# Gondola_Sail_electronics_M4_minimal.net
KiCad netlist of a schematic drawn in EAGLE
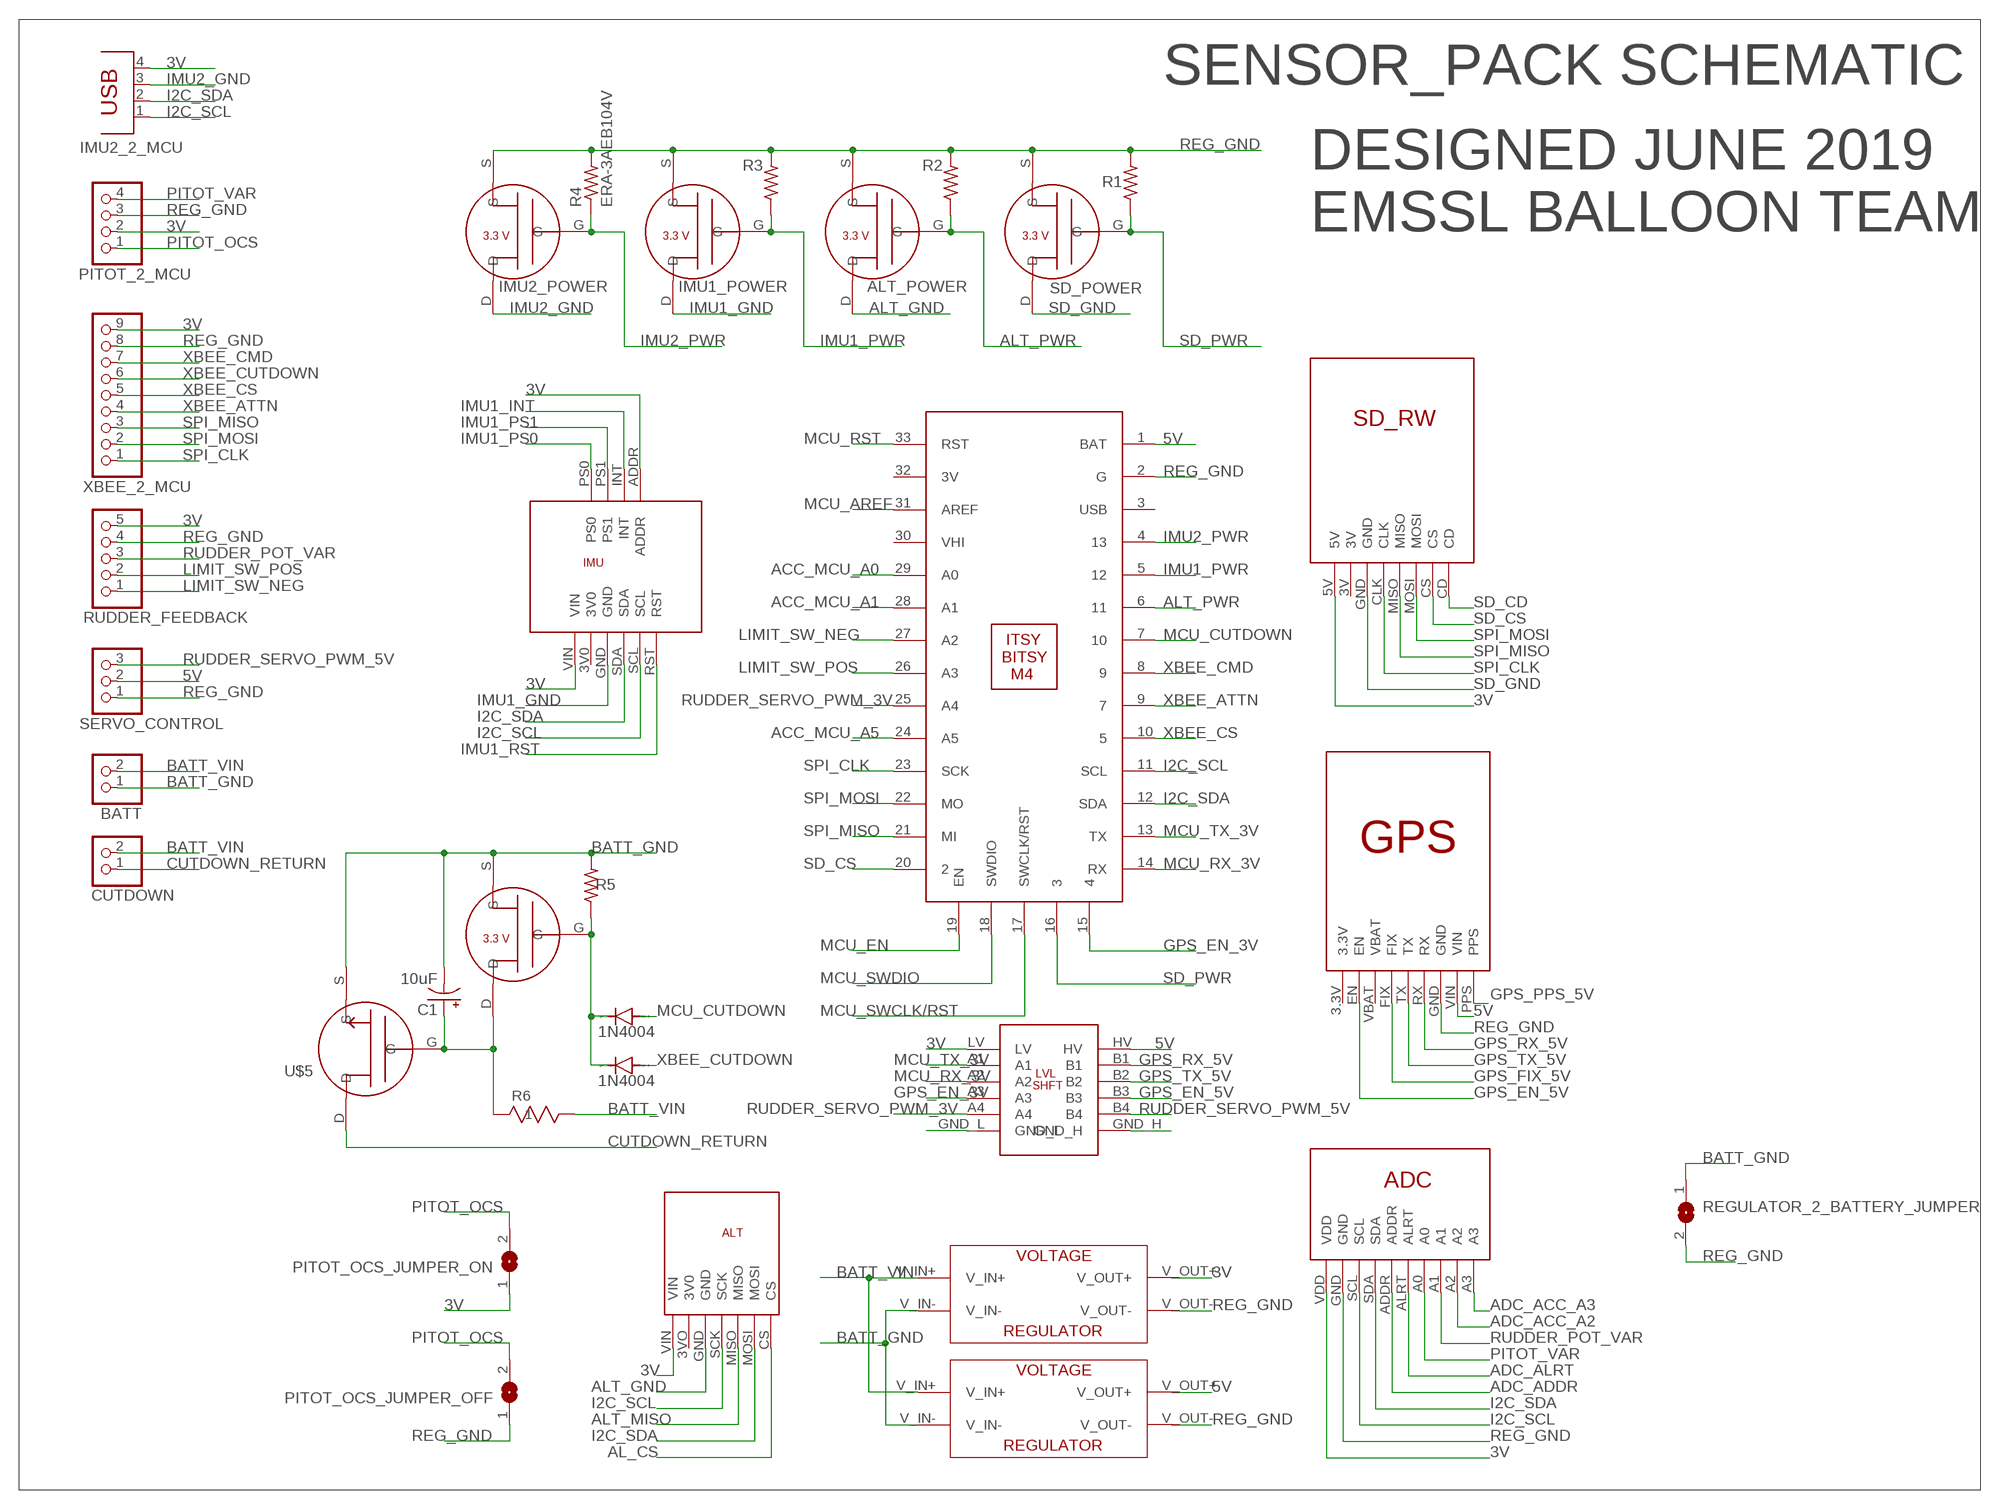
[diagram p0: schematic, sheet 1]

(export (version "E")
  (design (tool "Eeschema 10.0.6"))
  (components
    (comp (ref "3V_REG")
      (value "3V/5V_REGULATOR")
      (footprint "eagle-import:5V_3V_REGULATOR")
      (libsource (lib "eagle-import") (part "3V/5V_REGULATOR"))
    )
    (comp (ref "5V_REG")
      (value "3V/5V_REGULATOR")
      (footprint "eagle-import:5V_3V_REGULATOR")
      (libsource (lib "eagle-import") (part "3V/5V_REGULATOR"))
    )
    (comp (ref "ALT_POWER")
      (value "3.3V_NCH_FET")
      (footprint "eagle-import:3.3VTRANSISTOR")
      (libsource (lib "eagle-import") (part "3.3V_NCH_FET"))
    )
    (comp (ref "BATT")
      (value "PINHD-1X2/90")
      (footprint "eagle-import:1X02_90")
      (libsource (lib "eagle-import") (part "PINHD-1X2/90"))
    )
    (comp (ref "C1")
      (value "10uF")
      (footprint "eagle-import:CPOL-RADIAL-2.5MM-5MM")
      (libsource (lib "eagle-import") (part "10UF-POLAR-RADIAL-2.5MM-25V-20%"))
    )
    (comp (ref "CUTDOWN")
      (value "PINHD-1X2/90")
      (footprint "eagle-import:1X02_90")
      (libsource (lib "eagle-import") (part "PINHD-1X2/90"))
    )
    (comp (ref "D1")
      (value "1N4004")
      (footprint "eagle-import:DO41-10")
      (libsource (lib "eagle-import") (part "1N4004"))
    )
    (comp (ref "D2")
      (value "1N4004")
      (footprint "eagle-import:DO41-10")
      (libsource (lib "eagle-import") (part "1N4004"))
    )
    (comp (ref "IMU1")
      (value "BNO055")
      (footprint "eagle-import:BNO055")
      (libsource (lib "eagle-import") (part "BNO055"))
    )
    (comp (ref "IMU1_POWER")
      (value "3.3V_NCH_FET")
      (footprint "eagle-import:3.3VTRANSISTOR")
      (libsource (lib "eagle-import") (part "3.3V_NCH_FET"))
    )
    (comp (ref "IMU2_2_MCU")
      (value "PN87520")
      (footprint "eagle-import:PN87520")
      (libsource (lib "eagle-import") (part "PN87520"))
    )
    (comp (ref "IMU2_POWER")
      (value "3.3V_NCH_FET")
      (footprint "eagle-import:3.3VTRANSISTOR")
      (libsource (lib "eagle-import") (part "3.3V_NCH_FET"))
    )
    (comp (ref "PITOT_2_MCU")
      (value "PINHD-1X4/90")
      (footprint "eagle-import:1X04_90")
      (libsource (lib "eagle-import") (part "PINHD-1X4/90"))
    )
    (comp (ref "PITOT_OCS_JUMPER_OFF")
      (value "SJ")
      (footprint "eagle-import:SJ")
      (libsource (lib "eagle-import") (part "SJ"))
    )
    (comp (ref "PITOT_OCS_JUMPER_ON")
      (value "SJ")
      (footprint "eagle-import:SJ")
      (libsource (lib "eagle-import") (part "SJ"))
    )
    (comp (ref "R1")
      (value "ERA-3AEB104V")
      (footprint "eagle-import:RESC1608X55")
      (fields (field (name "DIGI-KEY_PART_NUMBER") "P100KDBCT-ND") (field (name "MF") "Panasonic"))
      (libsource (lib "eagle-import") (part "ERA-3AEB104V"))
    )
    (comp (ref "R2")
      (value "ERA-3AEB104V")
      (footprint "eagle-import:RESC1608X55")
      (fields (field (name "DIGI-KEY_PART_NUMBER") "P100KDBCT-ND") (field (name "MF") "Panasonic"))
      (libsource (lib "eagle-import") (part "ERA-3AEB104V"))
    )
    (comp (ref "R3")
      (value "ERA-3AEB104V")
      (footprint "eagle-import:RESC1608X55")
      (fields (field (name "DIGI-KEY_PART_NUMBER") "P100KDBCT-ND") (field (name "MF") "Panasonic"))
      (libsource (lib "eagle-import") (part "ERA-3AEB104V"))
    )
    (comp (ref "R4")
      (value "ERA-3AEB104V")
      (footprint "eagle-import:RESC1608X55")
      (fields (field (name "DIGI-KEY_PART_NUMBER") "P100KDBCT-ND") (field (name "MF") "Panasonic"))
      (libsource (lib "eagle-import") (part "ERA-3AEB104V"))
    )
    (comp (ref "R5")
      (value "ERA-3AEB104V")
      (footprint "eagle-import:RESC1608X55")
      (fields (field (name "DIGI-KEY_PART_NUMBER") "P100KDBCT-ND") (field (name "MF") "Panasonic"))
      (libsource (lib "eagle-import") (part "ERA-3AEB104V"))
    )
    (comp (ref "R6")
      (value "RR0816P-103-D")
      (footprint "eagle-import:RES_0816")
      (fields (field (name "MANUFACTURER_PART_NUMBER") "RR0816P103D"))
      (libsource (lib "eagle-import") (part "RR0816P-103-D"))
    )
    (comp (ref "REGULATOR_2_BATTERY_JUMPER")
      (value "SJW")
      (footprint "eagle-import:SJW")
      (libsource (lib "eagle-import") (part "SJW"))
    )
    (comp (ref "RUDDER_FEEDBACK")
      (value "PINHD-1X5/90")
      (footprint "eagle-import:1X05_90")
      (libsource (lib "eagle-import") (part "PINHD-1X5/90"))
    )
    (comp (ref "SD_POWER")
      (value "3.3V_NCH_FET")
      (footprint "eagle-import:3.3VTRANSISTOR")
      (libsource (lib "eagle-import") (part "3.3V_NCH_FET"))
    )
    (comp (ref "SD_POWER1")
      (value "3.3V_NCH_FET")
      (footprint "eagle-import:3.3VTRANSISTOR")
      (libsource (lib "eagle-import") (part "3.3V_NCH_FET"))
    )
    (comp (ref "SERVO_CONTROL")
      (value "PINHD-1X3/90")
      (footprint "eagle-import:1X03_90")
      (libsource (lib "eagle-import") (part "PINHD-1X3/90"))
    )
    (comp (ref "U$1")
      (value "ADAFRUIT_GPS")
      (footprint "eagle-import:ADAFRUIT_GPS")
      (libsource (lib "eagle-import") (part "ADAFRUIT_GPS"))
    )
    (comp (ref "U$2")
      (value "ADAFRUI_SD_RW")
      (footprint "eagle-import:ADAFRUIT_SD_RW")
      (libsource (lib "eagle-import") (part "ADAFRUI_SD_RW"))
    )
    (comp (ref "U$3")
      (value "ADS1115")
      (footprint "eagle-import:ADS1115")
      (libsource (lib "eagle-import") (part "ADS1115"))
    )
    (comp (ref "U$4")
      (value "BME280")
      (footprint "eagle-import:BME280")
      (libsource (lib "eagle-import") (part "BME280"))
    )
    (comp (ref "U$5")
      (value "CUTDOWN_POWER_TRANSISTOR")
      (footprint "eagle-import:T03B")
      (libsource (lib "eagle-import") (part "CUTDOWN_POWER_TRANSISTOR"))
    )
    (comp (ref "U$6")
      (value "BSS138_LVLSHIFT")
      (footprint "eagle-import:BSS138_LEVELSHIFT")
      (libsource (lib "eagle-import") (part "BSS138_LVLSHIFT"))
    )
    (comp (ref "U$8")
      (value "ITSY_BITSY_M4")
      (footprint "eagle-import:ITSY_BITSY_M4")
      (libsource (lib "eagle-import") (part "ITSY_BITSY_M4"))
    )
    (comp (ref "XBEE_2_MCU")
      (value "PINHD-1X9/90")
      (footprint "eagle-import:1X09_90")
      (libsource (lib "eagle-import") (part "PINHD-1X9/90"))
    )
  )
  (nets
    (net (code "1") (name "/3V") (class "Default")
      (node (ref "3V_REG") (pin "V_OUT+") (pinfunction "V_OUT+_V_OUT+") (pintype "bidirectional"))
      (node (ref "IMU1") (pin "ADDR") (pinfunction "ADDR_ADDR") (pintype "bidirectional"))
      (node (ref "IMU1") (pin "VIN") (pinfunction "VIN_VIN") (pintype "bidirectional"))
      (node (ref "IMU2_2_MCU") (pin "4") (pinfunction "4_4") (pintype "passive"))
      (node (ref "PITOT_2_MCU") (pin "2") (pinfunction "2_2") (pintype "passive"))
      (node (ref "PITOT_OCS_JUMPER_ON") (pin "1") (pinfunction "1_1") (pintype "passive"))
      (node (ref "RUDDER_FEEDBACK") (pin "5") (pinfunction "5_5") (pintype "passive"))
      (node (ref "U$2") (pin "5V") (pinfunction "5V_5V") (pintype "bidirectional"))
      (node (ref "U$3") (pin "VDD") (pinfunction "VDD_VDD") (pintype "bidirectional"))
      (node (ref "U$4") (pin "VIN") (pinfunction "VIN_VIN") (pintype "bidirectional"))
      (node (ref "U$6") (pin "LV") (pinfunction "LV_LV") (pintype "bidirectional"))
      (node (ref "XBEE_2_MCU") (pin "9") (pinfunction "9_9") (pintype "passive"))
    )
    (net (code "2") (name "/5V") (class "Default")
      (node (ref "5V_REG") (pin "V_OUT+") (pinfunction "V_OUT+_V_OUT+") (pintype "bidirectional"))
      (node (ref "SERVO_CONTROL") (pin "2") (pinfunction "2_2") (pintype "passive"))
      (node (ref "U$1") (pin "VIN") (pinfunction "VIN_VIN") (pintype "bidirectional"))
      (node (ref "U$6") (pin "HV") (pinfunction "HV_HV") (pintype "bidirectional"))
      (node (ref "U$8") (pin "1") (pinfunction "BAT_1") (pintype "output"))
    )
    (net (code "3") (name "/ACC_MCU_A0") (class "Default")
      (node (ref "U$8") (pin "29") (pinfunction "A0_29") (pintype "bidirectional"))
    )
    (net (code "4") (name "/ACC_MCU_A1") (class "Default")
      (node (ref "U$8") (pin "28") (pinfunction "A1_28") (pintype "bidirectional"))
    )
    (net (code "5") (name "/ACC_MCU_A5") (class "Default")
      (node (ref "U$8") (pin "24") (pinfunction "A5_24") (pintype "bidirectional"))
    )
    (net (code "6") (name "/ADC_ACC_A2") (class "Default")
      (node (ref "U$3") (pin "A2") (pinfunction "A2_A2") (pintype "bidirectional"))
    )
    (net (code "7") (name "/ADC_ACC_A3") (class "Default")
      (node (ref "U$3") (pin "A3") (pinfunction "A3_A3") (pintype "bidirectional"))
    )
    (net (code "8") (name "/ADC_ADDR") (class "Default")
      (node (ref "U$3") (pin "ADDR") (pinfunction "ADDR_ADDR") (pintype "bidirectional"))
    )
    (net (code "9") (name "/ADC_ALRT") (class "Default")
      (node (ref "U$3") (pin "ALRT") (pinfunction "ALRT_ALRT") (pintype "bidirectional"))
    )
    (net (code "10") (name "/ALT_GND") (class "Default")
      (node (ref "ALT_POWER") (pin "D") (pinfunction "D_D") (pintype "bidirectional"))
      (node (ref "U$4") (pin "GND") (pinfunction "GND_GND") (pintype "bidirectional"))
    )
    (net (code "11") (name "/ALT_MISO") (class "Default")
      (node (ref "U$4") (pin "MISO") (pinfunction "MISO_MISO") (pintype "bidirectional"))
    )
    (net (code "12") (name "/ALT_PWR") (class "Default")
      (node (ref "ALT_POWER") (pin "G") (pinfunction "G_G") (pintype "bidirectional"))
      (node (ref "R2") (pin "1") (pinfunction "1_1") (pintype "passive"))
      (node (ref "U$8") (pin "6") (pinfunction "11_6") (pintype "bidirectional"))
    )
    (net (code "13") (name "/AL_CS") (class "Default")
      (node (ref "U$4") (pin "CS") (pinfunction "CS_CS") (pintype "bidirectional"))
    )
    (net (code "14") (name "/BATT_GND") (class "Default")
      (node (ref "3V_REG") (pin "V_IN-") (pinfunction "V_IN-_V_IN-") (pintype "bidirectional"))
      (node (ref "5V_REG") (pin "V_IN-") (pinfunction "V_IN-_V_IN-") (pintype "bidirectional"))
      (node (ref "BATT") (pin "1") (pinfunction "1_1") (pintype "passive"))
      (node (ref "C1") (pin "2") (pinfunction "-_2") (pintype "passive"))
      (node (ref "R5") (pin "2") (pinfunction "2_2") (pintype "passive"))
      (node (ref "REGULATOR_2_BATTERY_JUMPER") (pin "1") (pinfunction "1_1") (pintype "passive"))
      (node (ref "SD_POWER1") (pin "S") (pinfunction "S_S") (pintype "bidirectional"))
      (node (ref "U$5") (pin "S") (pinfunction "S_S") (pintype "bidirectional"))
    )
    (net (code "15") (name "/BATT_VIN") (class "Default")
      (node (ref "3V_REG") (pin "V_IN+") (pinfunction "V_IN+_V_IN+") (pintype "bidirectional"))
      (node (ref "5V_REG") (pin "V_IN+") (pinfunction "V_IN+_V_IN+") (pintype "bidirectional"))
      (node (ref "BATT") (pin "2") (pinfunction "2_2") (pintype "passive"))
      (node (ref "CUTDOWN") (pin "2") (pinfunction "2_2") (pintype "passive"))
      (node (ref "R6") (pin "2") (pinfunction "2_2") (pintype "passive"))
    )
    (net (code "16") (name "/CUTDOWN_RETURN") (class "Default")
      (node (ref "CUTDOWN") (pin "1") (pinfunction "1_1") (pintype "passive"))
      (node (ref "U$5") (pin "D") (pinfunction "D_D") (pintype "bidirectional"))
    )
    (net (code "17") (name "/GPS_EN_3V") (class "Default")
      (node (ref "U$6") (pin "A3") (pinfunction "A3_A3") (pintype "bidirectional"))
      (node (ref "U$8") (pin "15") (pinfunction "4_15") (pintype "bidirectional"))
    )
    (net (code "18") (name "/GPS_EN_5V") (class "Default")
      (node (ref "U$1") (pin "EN") (pinfunction "EN_EN") (pintype "bidirectional"))
      (node (ref "U$6") (pin "B3") (pinfunction "B3_B3") (pintype "bidirectional"))
    )
    (net (code "19") (name "/GPS_FIX_5V") (class "Default")
      (node (ref "U$1") (pin "FIX") (pinfunction "FIX_FIX") (pintype "bidirectional"))
    )
    (net (code "20") (name "/GPS_PPS_5V") (class "Default")
      (node (ref "U$1") (pin "PPS") (pinfunction "PPS_PPS") (pintype "bidirectional"))
    )
    (net (code "21") (name "/GPS_RX_5V") (class "Default")
      (node (ref "U$1") (pin "RX") (pinfunction "RX_RX") (pintype "bidirectional"))
      (node (ref "U$6") (pin "B1") (pinfunction "B1_B1") (pintype "bidirectional"))
    )
    (net (code "22") (name "/GPS_TX_5V") (class "Default")
      (node (ref "U$1") (pin "TX") (pinfunction "TX_TX") (pintype "bidirectional"))
      (node (ref "U$6") (pin "B2") (pinfunction "B2_B2") (pintype "bidirectional"))
    )
    (net (code "23") (name "/I2C_SCL") (class "Default")
      (node (ref "IMU1") (pin "SCL") (pinfunction "SCL_SCL") (pintype "bidirectional"))
      (node (ref "IMU2_2_MCU") (pin "1") (pinfunction "1_1") (pintype "passive"))
      (node (ref "U$3") (pin "SCL") (pinfunction "SCL_SCL") (pintype "bidirectional"))
      (node (ref "U$4") (pin "SCK") (pinfunction "SCK_SCK") (pintype "bidirectional"))
      (node (ref "U$8") (pin "11") (pinfunction "SCL_11") (pintype "bidirectional"))
    )
    (net (code "24") (name "/I2C_SDA") (class "Default")
      (node (ref "IMU1") (pin "SDA") (pinfunction "SDA_SDA") (pintype "bidirectional"))
      (node (ref "IMU2_2_MCU") (pin "2") (pinfunction "2_2") (pintype "passive"))
      (node (ref "U$3") (pin "SDA") (pinfunction "SDA_SDA") (pintype "bidirectional"))
      (node (ref "U$4") (pin "MOSI") (pinfunction "MOSI_MOSI") (pintype "bidirectional"))
      (node (ref "U$8") (pin "12") (pinfunction "SDA_12") (pintype "bidirectional"))
    )
    (net (code "25") (name "/IMU1_GND") (class "Default")
      (node (ref "IMU1") (pin "GND") (pinfunction "GND_GND") (pintype "bidirectional"))
      (node (ref "IMU1_POWER") (pin "D") (pinfunction "D_D") (pintype "bidirectional"))
    )
    (net (code "26") (name "/IMU1_INT") (class "Default")
      (node (ref "IMU1") (pin "INT") (pinfunction "INT_INT") (pintype "bidirectional"))
    )
    (net (code "27") (name "/IMU1_PS0") (class "Default")
      (node (ref "IMU1") (pin "PS0") (pinfunction "PS0_PS0") (pintype "bidirectional"))
    )
    (net (code "28") (name "/IMU1_PS1") (class "Default")
      (node (ref "IMU1") (pin "PS1") (pinfunction "PS1_PS1") (pintype "bidirectional"))
    )
    (net (code "29") (name "/IMU1_PWR") (class "Default")
      (node (ref "IMU1_POWER") (pin "G") (pinfunction "G_G") (pintype "bidirectional"))
      (node (ref "R3") (pin "1") (pinfunction "1_1") (pintype "passive"))
      (node (ref "U$8") (pin "5") (pinfunction "12_5") (pintype "bidirectional"))
    )
    (net (code "30") (name "/IMU1_RST") (class "Default")
      (node (ref "IMU1") (pin "RST") (pinfunction "RST_RST") (pintype "bidirectional"))
    )
    (net (code "31") (name "/IMU2_GND") (class "Default")
      (node (ref "IMU2_2_MCU") (pin "3") (pinfunction "3_3") (pintype "passive"))
      (node (ref "IMU2_POWER") (pin "D") (pinfunction "D_D") (pintype "bidirectional"))
    )
    (net (code "32") (name "/IMU2_PWR") (class "Default")
      (node (ref "IMU2_POWER") (pin "G") (pinfunction "G_G") (pintype "bidirectional"))
      (node (ref "R4") (pin "1") (pinfunction "1_1") (pintype "passive"))
      (node (ref "U$8") (pin "4") (pinfunction "13_4") (pintype "bidirectional"))
    )
    (net (code "33") (name "/LIMIT_SW_NEG") (class "Default")
      (node (ref "RUDDER_FEEDBACK") (pin "1") (pinfunction "1_1") (pintype "passive"))
      (node (ref "U$8") (pin "27") (pinfunction "A2_27") (pintype "bidirectional"))
    )
    (net (code "34") (name "/LIMIT_SW_POS") (class "Default")
      (node (ref "RUDDER_FEEDBACK") (pin "2") (pinfunction "2_2") (pintype "passive"))
      (node (ref "U$8") (pin "26") (pinfunction "A3_26") (pintype "bidirectional"))
    )
    (net (code "35") (name "/MCU_AREF") (class "Default")
      (node (ref "U$8") (pin "31") (pinfunction "AREF_31") (pintype "bidirectional"))
    )
    (net (code "36") (name "/MCU_CUTDOWN") (class "Default")
      (node (ref "D1") (pin "A") (pinfunction "A_A") (pintype "passive"))
      (node (ref "U$8") (pin "7") (pinfunction "10_7") (pintype "bidirectional"))
    )
    (net (code "37") (name "/MCU_EN") (class "Default")
      (node (ref "U$8") (pin "19") (pinfunction "EN_19") (pintype "bidirectional"))
    )
    (net (code "38") (name "/MCU_RST") (class "Default")
      (node (ref "U$8") (pin "33") (pinfunction "RST_33") (pintype "bidirectional"))
    )
    (net (code "39") (name "/MCU_RX_3V") (class "Default")
      (node (ref "U$6") (pin "A2") (pinfunction "A2_A2") (pintype "bidirectional"))
      (node (ref "U$8") (pin "14") (pinfunction "RX_14") (pintype "bidirectional"))
    )
    (net (code "40") (name "/MCU_SWCLK{slash}RST") (class "Default")
      (node (ref "U$8") (pin "17") (pinfunction "SWCLK/RST_17") (pintype "bidirectional"))
    )
    (net (code "41") (name "/MCU_SWDIO") (class "Default")
      (node (ref "U$8") (pin "18") (pinfunction "SWDIO_18") (pintype "bidirectional"))
    )
    (net (code "42") (name "/MCU_TX_3V") (class "Default")
      (node (ref "U$6") (pin "A1") (pinfunction "A1_A1") (pintype "bidirectional"))
      (node (ref "U$8") (pin "13") (pinfunction "TX_13") (pintype "bidirectional"))
    )
    (net (code "43") (name "/PITOT_OCS") (class "Default")
      (node (ref "PITOT_2_MCU") (pin "1") (pinfunction "1_1") (pintype "passive"))
      (node (ref "PITOT_OCS_JUMPER_OFF") (pin "2") (pinfunction "2_2") (pintype "passive"))
      (node (ref "PITOT_OCS_JUMPER_ON") (pin "2") (pinfunction "2_2") (pintype "passive"))
    )
    (net (code "44") (name "/PITOT_VAR") (class "Default")
      (node (ref "PITOT_2_MCU") (pin "4") (pinfunction "4_4") (pintype "passive"))
      (node (ref "U$3") (pin "A0") (pinfunction "A0_A0") (pintype "bidirectional"))
    )
    (net (code "45") (name "/REG_GND") (class "Default")
      (node (ref "3V_REG") (pin "V_OUT-") (pinfunction "V_OUT-_V_OUT-") (pintype "bidirectional"))
      (node (ref "5V_REG") (pin "V_OUT-") (pinfunction "V_OUT-_V_OUT-") (pintype "bidirectional"))
      (node (ref "ALT_POWER") (pin "S") (pinfunction "S_S") (pintype "bidirectional"))
      (node (ref "IMU1_POWER") (pin "S") (pinfunction "S_S") (pintype "bidirectional"))
      (node (ref "IMU2_POWER") (pin "S") (pinfunction "S_S") (pintype "bidirectional"))
      (node (ref "PITOT_2_MCU") (pin "3") (pinfunction "3_3") (pintype "passive"))
      (node (ref "PITOT_OCS_JUMPER_OFF") (pin "1") (pinfunction "1_1") (pintype "passive"))
      (node (ref "R1") (pin "2") (pinfunction "2_2") (pintype "passive"))
      (node (ref "R2") (pin "2") (pinfunction "2_2") (pintype "passive"))
      (node (ref "R3") (pin "2") (pinfunction "2_2") (pintype "passive"))
      (node (ref "R4") (pin "2") (pinfunction "2_2") (pintype "passive"))
      (node (ref "REGULATOR_2_BATTERY_JUMPER") (pin "2") (pinfunction "2_2") (pintype "passive"))
      (node (ref "RUDDER_FEEDBACK") (pin "4") (pinfunction "4_4") (pintype "passive"))
      (node (ref "SD_POWER") (pin "S") (pinfunction "S_S") (pintype "bidirectional"))
      (node (ref "SERVO_CONTROL") (pin "1") (pinfunction "1_1") (pintype "passive"))
      (node (ref "U$1") (pin "GND") (pinfunction "GND_GND") (pintype "bidirectional"))
      (node (ref "U$3") (pin "GND") (pinfunction "GND_GND") (pintype "bidirectional"))
      (node (ref "U$8") (pin "2") (pinfunction "G_2") (pintype "bidirectional"))
      (node (ref "XBEE_2_MCU") (pin "8") (pinfunction "8_8") (pintype "passive"))
    )
    (net (code "46") (name "/RUDDER_POT_VAR") (class "Default")
      (node (ref "RUDDER_FEEDBACK") (pin "3") (pinfunction "3_3") (pintype "passive"))
      (node (ref "U$3") (pin "A1") (pinfunction "A1_A1") (pintype "bidirectional"))
    )
    (net (code "47") (name "/RUDDER_SERVO_PWM_3V") (class "Default")
      (node (ref "U$6") (pin "A4") (pinfunction "A4_A4") (pintype "bidirectional"))
      (node (ref "U$8") (pin "25") (pinfunction "A4_25") (pintype "bidirectional"))
    )
    (net (code "48") (name "/RUDDER_SERVO_PWM_5V") (class "Default")
      (node (ref "SERVO_CONTROL") (pin "3") (pinfunction "3_3") (pintype "passive"))
      (node (ref "U$6") (pin "B4") (pinfunction "B4_B4") (pintype "bidirectional"))
    )
    (net (code "49") (name "/SD_CD") (class "Default")
      (node (ref "U$2") (pin "CD") (pinfunction "CD_CD") (pintype "bidirectional"))
    )
    (net (code "50") (name "/SD_CS") (class "Default")
      (node (ref "U$2") (pin "CS") (pinfunction "CS_CS") (pintype "bidirectional"))
      (node (ref "U$8") (pin "20") (pinfunction "2_20") (pintype "bidirectional"))
    )
    (net (code "51") (name "/SD_GND") (class "Default")
      (node (ref "SD_POWER") (pin "D") (pinfunction "D_D") (pintype "bidirectional"))
      (node (ref "U$2") (pin "GND") (pinfunction "GND_GND") (pintype "bidirectional"))
    )
    (net (code "52") (name "/SD_PWR") (class "Default")
      (node (ref "R1") (pin "1") (pinfunction "1_1") (pintype "passive"))
      (node (ref "SD_POWER") (pin "G") (pinfunction "G_G") (pintype "bidirectional"))
      (node (ref "U$8") (pin "16") (pinfunction "3_16") (pintype "bidirectional"))
    )
    (net (code "53") (name "/SPI_CLK") (class "Default")
      (node (ref "U$2") (pin "CLK") (pinfunction "CLK_CLK") (pintype "bidirectional"))
      (node (ref "U$8") (pin "23") (pinfunction "SCK_23") (pintype "bidirectional"))
      (node (ref "XBEE_2_MCU") (pin "1") (pinfunction "1_1") (pintype "passive"))
    )
    (net (code "54") (name "/SPI_MISO") (class "Default")
      (node (ref "U$2") (pin "MISO") (pinfunction "MISO_MISO") (pintype "bidirectional"))
      (node (ref "U$8") (pin "21") (pinfunction "MI_21") (pintype "bidirectional"))
      (node (ref "XBEE_2_MCU") (pin "3") (pinfunction "3_3") (pintype "passive"))
    )
    (net (code "55") (name "/SPI_MOSI") (class "Default")
      (node (ref "U$2") (pin "MOSI") (pinfunction "MOSI_MOSI") (pintype "bidirectional"))
      (node (ref "U$8") (pin "22") (pinfunction "MO_22") (pintype "bidirectional"))
      (node (ref "XBEE_2_MCU") (pin "2") (pinfunction "2_2") (pintype "passive"))
    )
    (net (code "56") (name "/XBEE_ATTN") (class "Default")
      (node (ref "U$8") (pin "9") (pinfunction "7_9") (pintype "bidirectional"))
      (node (ref "XBEE_2_MCU") (pin "4") (pinfunction "4_4") (pintype "passive"))
    )
    (net (code "57") (name "/XBEE_CMD") (class "Default")
      (node (ref "U$8") (pin "8") (pinfunction "9_8") (pintype "bidirectional"))
      (node (ref "XBEE_2_MCU") (pin "7") (pinfunction "7_7") (pintype "passive"))
    )
    (net (code "58") (name "/XBEE_CS") (class "Default")
      (node (ref "U$8") (pin "10") (pinfunction "5_10") (pintype "bidirectional"))
      (node (ref "XBEE_2_MCU") (pin "5") (pinfunction "5_5") (pintype "passive"))
    )
    (net (code "59") (name "/XBEE_CUTDOWN") (class "Default")
      (node (ref "D2") (pin "A") (pinfunction "A_A") (pintype "passive"))
      (node (ref "XBEE_2_MCU") (pin "6") (pinfunction "6_6") (pintype "passive"))
    )
    (net (code "60") (name "Net-(C1-+)") (class "Default")
      (node (ref "C1") (pin "1") (pinfunction "+_1") (pintype "passive"))
      (node (ref "R6") (pin "1") (pinfunction "1_1") (pintype "passive"))
      (node (ref "SD_POWER1") (pin "D") (pinfunction "D_D") (pintype "bidirectional"))
      (node (ref "U$5") (pin "G") (pinfunction "G_G") (pintype "bidirectional"))
    )
    (net (code "61") (name "Net-(D1-PadC)") (class "Default")
      (node (ref "D1") (pin "C") (pinfunction "C_C") (pintype "passive"))
      (node (ref "D2") (pin "C") (pinfunction "C_C") (pintype "passive"))
      (node (ref "R5") (pin "1") (pinfunction "1_1") (pintype "passive"))
      (node (ref "SD_POWER1") (pin "G") (pinfunction "G_G") (pintype "bidirectional"))
    )
    (net (code "62") (name "unconnected-(IMU1-Pad3V0)") (class "Default")
      (node (ref "IMU1") (pin "3V0") (pinfunction "3V0_3V0") (pintype "bidirectional"))
    )
    (net (code "63") (name "unconnected-(U$1-Pad3.3V)") (class "Default")
      (node (ref "U$1") (pin "3.3V") (pinfunction "3.3V_3.3V") (pintype "bidirectional"))
    )
    (net (code "64") (name "unconnected-(U$1-PadVBAT)") (class "Default")
      (node (ref "U$1") (pin "VBAT") (pinfunction "VBAT_VBAT") (pintype "bidirectional"))
    )
    (net (code "65") (name "unconnected-(U$2-Pad3V)") (class "Default")
      (node (ref "U$2") (pin "3V") (pinfunction "3V_3V") (pintype "bidirectional"))
    )
    (net (code "66") (name "unconnected-(U$4-3V0-Pad3VO)") (class "Default")
      (node (ref "U$4") (pin "3VO") (pinfunction "3V0_3VO") (pintype "bidirectional"))
    )
    (net (code "67") (name "unconnected-(U$6-PadGND_H)") (class "Default")
      (node (ref "U$6") (pin "GND_H") (pinfunction "GND_H_GND_H") (pintype "bidirectional"))
    )
    (net (code "68") (name "unconnected-(U$6-PadGND_L)") (class "Default")
      (node (ref "U$6") (pin "GND_L") (pinfunction "GND_L_GND_L") (pintype "bidirectional"))
    )
    (net (code "69") (name "unconnected-(U$8-3V-Pad32)") (class "Default")
      (node (ref "U$8") (pin "32") (pinfunction "3V_32") (pintype "bidirectional"))
    )
    (net (code "70") (name "unconnected-(U$8-USB-Pad3)") (class "Default")
      (node (ref "U$8") (pin "3") (pinfunction "USB_3") (pintype "bidirectional"))
    )
    (net (code "71") (name "unconnected-(U$8-VHI-Pad30)") (class "Default")
      (node (ref "U$8") (pin "30") (pinfunction "VHI_30") (pintype "bidirectional"))
    )
  )
)
